# sb4.net
KiCad netlist of a schematic drawn in EAGLE
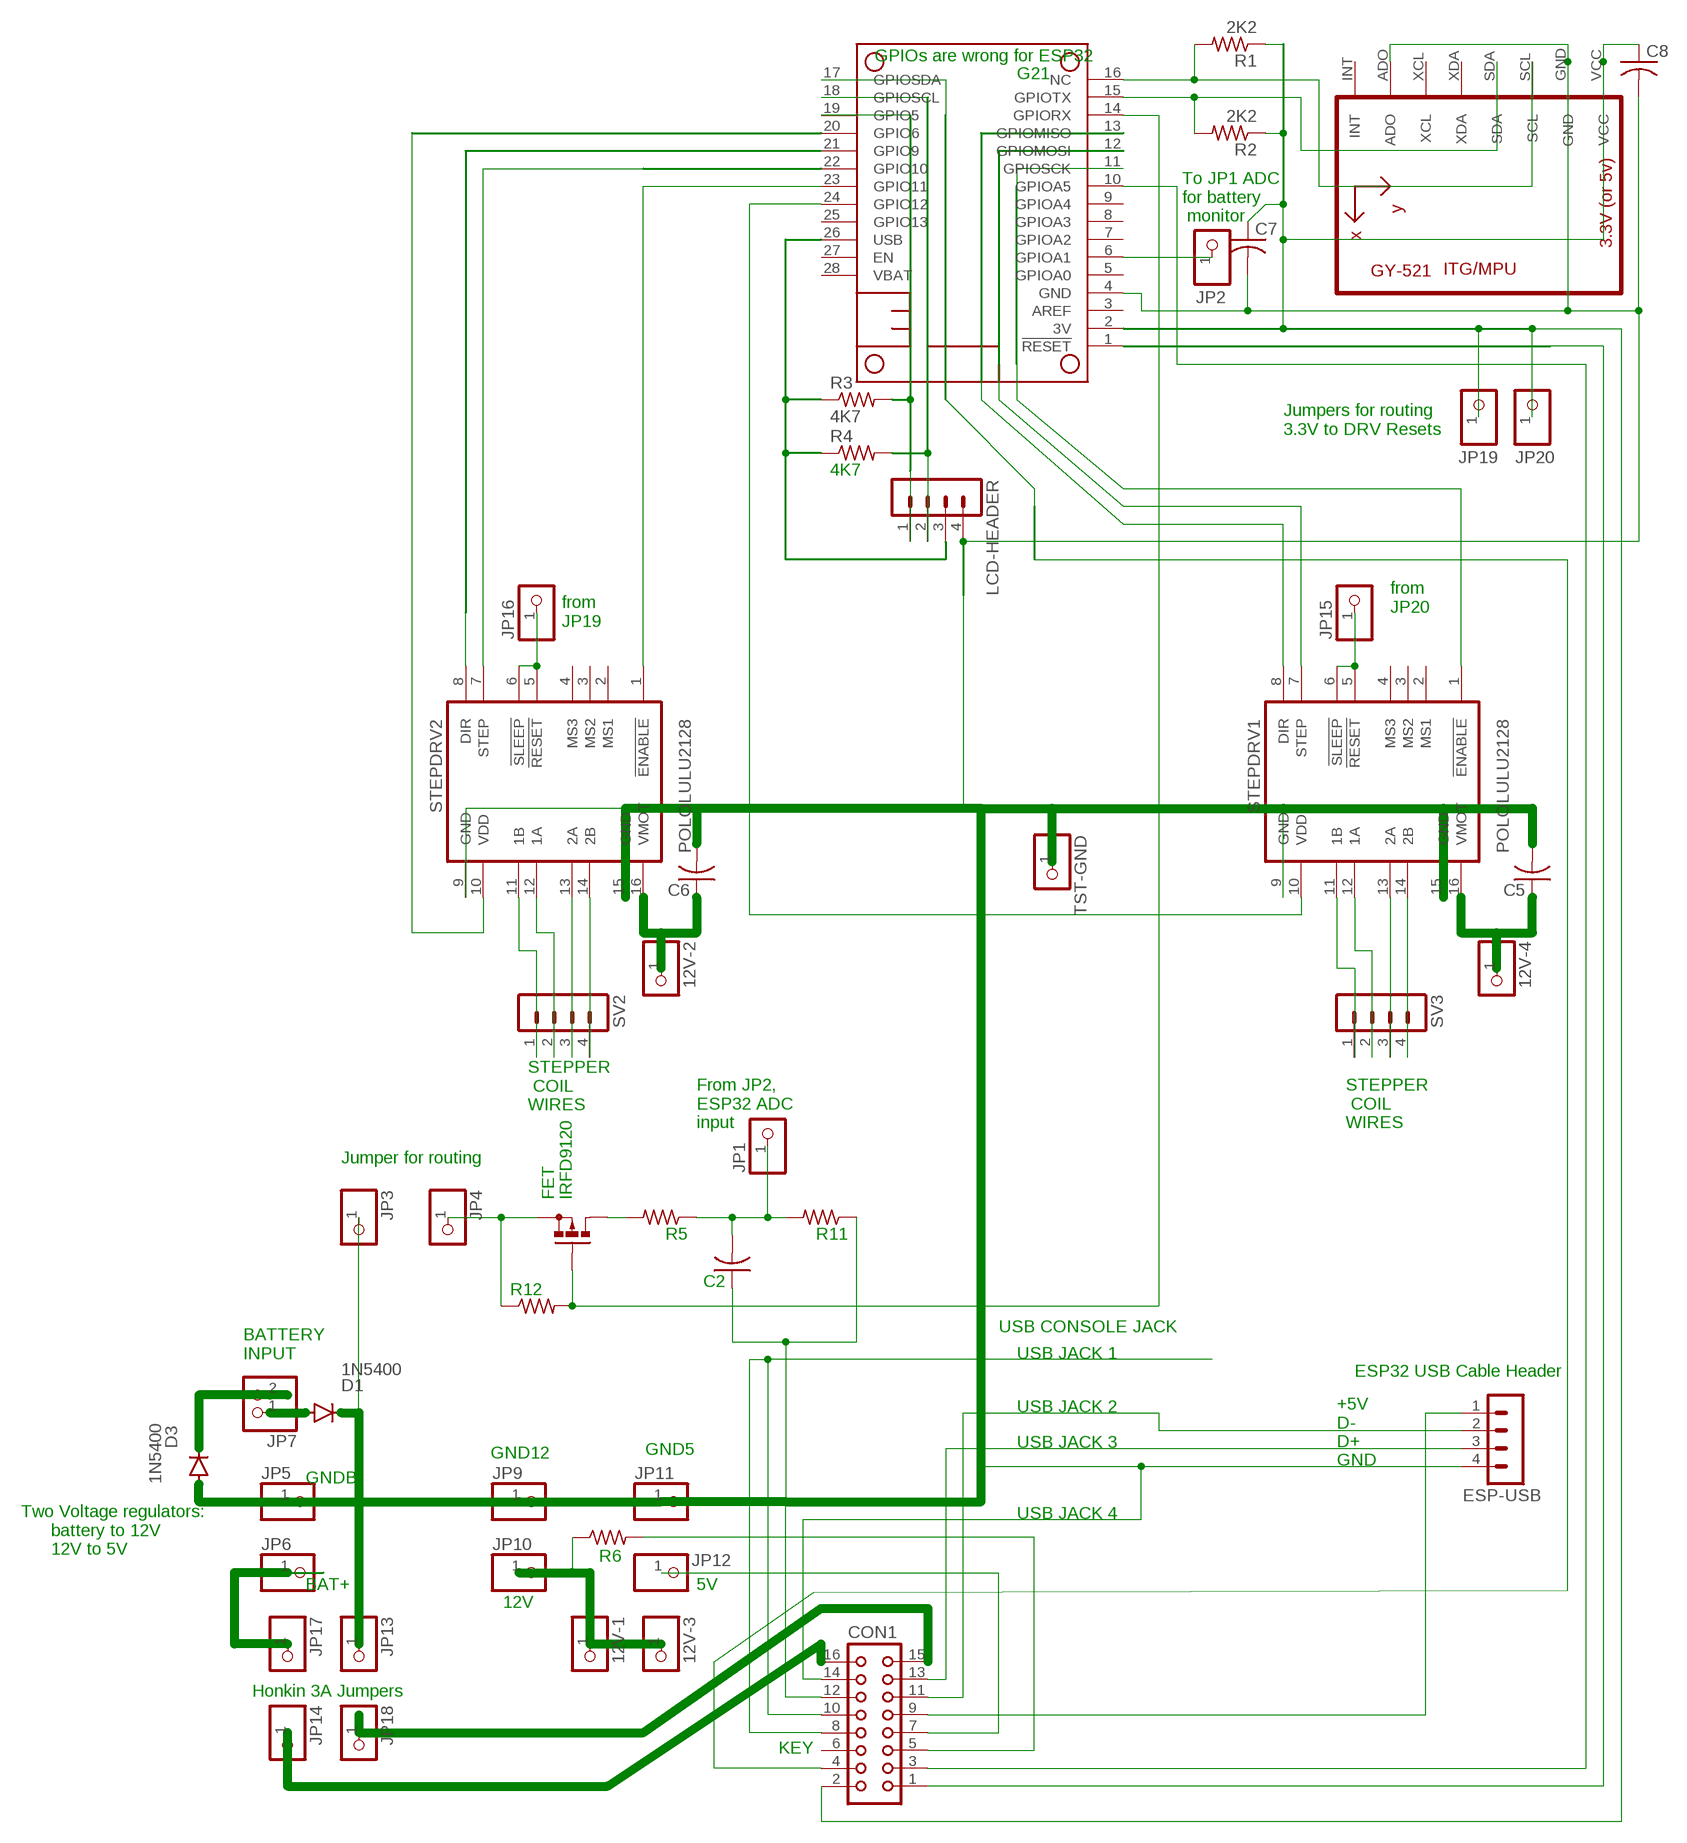
[diagram p0: schematic, sheet 1]

(export (version "E")
  (design (tool "Eeschema 10.0.6"))
  (components
    (comp (ref "12V-1")
      (value "PINHD-1X1")
      (footprint "eagle-import:1X01")
      (libsource (lib "eagle-import") (part "PINHD-1X1"))
    )
    (comp (ref "12V-2")
      (value "PINHD-1X1")
      (footprint "eagle-import:1X01")
      (libsource (lib "eagle-import") (part "PINHD-1X1"))
    )
    (comp (ref "12V-3")
      (value "PINHD-1X1")
      (footprint "eagle-import:1X01")
      (libsource (lib "eagle-import") (part "PINHD-1X1"))
    )
    (comp (ref "12V-4")
      (value "PINHD-1X1")
      (footprint "eagle-import:1X01")
      (libsource (lib "eagle-import") (part "PINHD-1X1"))
    )
    (comp (ref "C2")
      (value "C-US050-025X075")
      (footprint "eagle-import:C050-025X075")
      (libsource (lib "eagle-import") (part "C-US050-025X075"))
    )
    (comp (ref "C5")
      (value "C-US050-024X044")
      (footprint "eagle-import:C050-024X044")
      (libsource (lib "eagle-import") (part "C-US050-024X044"))
    )
    (comp (ref "C6")
      (value "C-US050-024X044")
      (footprint "eagle-import:C050-024X044")
      (libsource (lib "eagle-import") (part "C-US050-024X044"))
    )
    (comp (ref "C7")
      (value "C-US050-024X044")
      (footprint "eagle-import:C050-024X044")
      (libsource (lib "eagle-import") (part "C-US050-024X044"))
    )
    (comp (ref "C8")
      (value "C-US050-024X044")
      (footprint "eagle-import:C050-024X044")
      (libsource (lib "eagle-import") (part "C-US050-024X044"))
    )
    (comp (ref "CON1")
      (value "CON16")
      (footprint "eagle-import:CON16")
      (libsource (lib "eagle-import") (part "CON16"))
    )
    (comp (ref "D1")
      (value "1N5400")
      (footprint "eagle-import:DO201-15")
      (libsource (lib "eagle-import") (part "1N5400"))
    )
    (comp (ref "D3")
      (value "1N5400")
      (footprint "eagle-import:DO201-15")
      (libsource (lib "eagle-import") (part "1N5400"))
    )
    (comp (ref "ESP-USB")
      (value "MA04-1")
      (footprint "eagle-import:MA04-1")
      (libsource (lib "eagle-import") (part "MA04-1"))
    )
    (comp (ref "FET")
      (value "IRFD9120")
      (footprint "eagle-import:C370-01")
      (libsource (lib "eagle-import") (part "IRFD9120"))
    )
    (comp (ref "JP1")
      (value "PINHD-1X1")
      (footprint "eagle-import:1X01")
      (libsource (lib "eagle-import") (part "PINHD-1X1"))
    )
    (comp (ref "JP2")
      (value "PINHD-1X1")
      (footprint "eagle-import:1X01")
      (libsource (lib "eagle-import") (part "PINHD-1X1"))
    )
    (comp (ref "JP3")
      (value "PINHD-1X1")
      (footprint "eagle-import:1X01")
      (libsource (lib "eagle-import") (part "PINHD-1X1"))
    )
    (comp (ref "JP4")
      (value "PINHD-1X1")
      (footprint "eagle-import:1X01")
      (libsource (lib "eagle-import") (part "PINHD-1X1"))
    )
    (comp (ref "JP5")
      (value "PINHD-1X1")
      (footprint "eagle-import:1X01")
      (libsource (lib "eagle-import") (part "PINHD-1X1"))
    )
    (comp (ref "JP6")
      (value "PINHD-1X1")
      (footprint "eagle-import:1X01")
      (libsource (lib "eagle-import") (part "PINHD-1X1"))
    )
    (comp (ref "JP7")
      (value "PINHD-1X2")
      (footprint "eagle-import:1X02")
      (libsource (lib "eagle-import") (part "PINHD-1X2"))
    )
    (comp (ref "JP9")
      (value "PINHD-1X1")
      (footprint "eagle-import:1X01")
      (libsource (lib "eagle-import") (part "PINHD-1X1"))
    )
    (comp (ref "JP10")
      (value "PINHD-1X1")
      (footprint "eagle-import:1X01")
      (libsource (lib "eagle-import") (part "PINHD-1X1"))
    )
    (comp (ref "JP11")
      (value "PINHD-1X1")
      (footprint "eagle-import:1X01")
      (libsource (lib "eagle-import") (part "PINHD-1X1"))
    )
    (comp (ref "JP12")
      (value "PINHD-1X1")
      (footprint "eagle-import:1X01")
      (libsource (lib "eagle-import") (part "PINHD-1X1"))
    )
    (comp (ref "JP13")
      (value "PINHD-1X1")
      (footprint "eagle-import:1X01")
      (libsource (lib "eagle-import") (part "PINHD-1X1"))
    )
    (comp (ref "JP14")
      (value "PINHD-1X1")
      (footprint "eagle-import:1X01")
      (libsource (lib "eagle-import") (part "PINHD-1X1"))
    )
    (comp (ref "JP15")
      (value "PINHD-1X1")
      (footprint "eagle-import:1X01")
      (libsource (lib "eagle-import") (part "PINHD-1X1"))
    )
    (comp (ref "JP16")
      (value "PINHD-1X1")
      (footprint "eagle-import:1X01")
      (libsource (lib "eagle-import") (part "PINHD-1X1"))
    )
    (comp (ref "JP17")
      (value "PINHD-1X1")
      (footprint "eagle-import:1X01")
      (libsource (lib "eagle-import") (part "PINHD-1X1"))
    )
    (comp (ref "JP18")
      (value "PINHD-1X1")
      (footprint "eagle-import:1X01")
      (libsource (lib "eagle-import") (part "PINHD-1X1"))
    )
    (comp (ref "JP19")
      (value "PINHD-1X1")
      (footprint "eagle-import:1X01")
      (libsource (lib "eagle-import") (part "PINHD-1X1"))
    )
    (comp (ref "JP20")
      (value "PINHD-1X1")
      (footprint "eagle-import:1X01")
      (libsource (lib "eagle-import") (part "PINHD-1X1"))
    )
    (comp (ref "LCD-HEADER")
      (value "MA04-1")
      (footprint "eagle-import:MA04-1")
      (libsource (lib "eagle-import") (part "MA04-1"))
    )
    (comp (ref "MS2")
      (value "FEATHERWING_NOHOLES")
      (footprint "eagle-import:FEATHERWING_NOHOLES")
      (libsource (lib "eagle-import") (part "FEATHERWING_NOHOLES"))
    )
    (comp (ref "R1")
      (value "2K2")
      (footprint "eagle-import:0309_12")
      (libsource (lib "eagle-import") (part "resistor_348_R-US_0309/12"))
    )
    (comp (ref "R2")
      (value "2K2")
      (footprint "eagle-import:0309_12")
      (libsource (lib "eagle-import") (part "resistor_348_R-US_0309/12"))
    )
    (comp (ref "R3")
      (value "4K7")
      (footprint "eagle-import:0309_12")
      (libsource (lib "eagle-import") (part "resistor_348_R-US_0309/12"))
    )
    (comp (ref "R4")
      (value "4K7")
      (footprint "eagle-import:0309_12")
      (libsource (lib "eagle-import") (part "resistor_348_R-US_0309/12"))
    )
    (comp (ref "R5")
      (value "R-US_0207/10")
      (footprint "eagle-import:0207_10")
      (libsource (lib "eagle-import") (part "R-US_0207/10"))
    )
    (comp (ref "R6")
      (value "R-US_0207/10")
      (footprint "eagle-import:0207_10")
      (libsource (lib "eagle-import") (part "R-US_0207/10"))
    )
    (comp (ref "R11")
      (value "R-US_0207/10")
      (footprint "eagle-import:0207_10")
      (libsource (lib "eagle-import") (part "R-US_0207/10"))
    )
    (comp (ref "R12")
      (value "R-US_0207/10")
      (footprint "eagle-import:0207_10")
      (libsource (lib "eagle-import") (part "R-US_0207/10"))
    )
    (comp (ref "STEPDRV1")
      (value "POLOLULU2128")
      (footprint "eagle-import:POLOLULU2128")
      (libsource (lib "eagle-import") (part "POLOLULU2128"))
    )
    (comp (ref "STEPDRV2")
      (value "POLOLULU2128")
      (footprint "eagle-import:POLOLULU2128")
      (libsource (lib "eagle-import") (part "POLOLULU2128"))
    )
    (comp (ref "SV2")
      (value "MA04-1")
      (footprint "eagle-import:MA04-1")
      (libsource (lib "eagle-import") (part "MA04-1"))
    )
    (comp (ref "SV3")
      (value "MA04-1")
      (footprint "eagle-import:MA04-1")
      (libsource (lib "eagle-import") (part "MA04-1"))
    )
    (comp (ref "TST-GND")
      (value "PINHD-1X1")
      (footprint "eagle-import:1X01")
      (libsource (lib "eagle-import") (part "PINHD-1X1"))
    )
    (comp (ref "U1")
      (value "GY-521MPU6050")
      (footprint "eagle-import:GY-521")
      (libsource (lib "eagle-import") (part "GY-521MPU6050"))
    )
  )
  (nets
    (net (code "1") (name "/VBAT") (class "Default")
      (node (ref "MS2") (pin "28") (pinfunction "VBAT_28") (pintype "power_in"))
    )
    (net (code "2") (name "Net-(12V-1-Pad1)") (class "Default")
      (node (ref "12V-1") (pin "1") (pinfunction "1_1") (pintype "passive"))
      (node (ref "12V-3") (pin "1") (pinfunction "1_1") (pintype "passive"))
      (node (ref "JP10") (pin "1") (pinfunction "1_1") (pintype "passive"))
      (node (ref "R6") (pin "1") (pinfunction "1_1") (pintype "passive"))
    )
    (net (code "3") (name "Net-(C2-Pad2)") (class "Default")
      (node (ref "C2") (pin "2") (pinfunction "2_2") (pintype "passive"))
      (node (ref "JP1") (pin "1") (pinfunction "1_1") (pintype "passive"))
      (node (ref "R11") (pin "2") (pinfunction "2_2") (pintype "passive"))
      (node (ref "R5") (pin "1") (pinfunction "1_1") (pintype "passive"))
    )
    (net (code "4") (name "Net-(CON1-Pad5)") (class "Default")
      (node (ref "CON1") (pin "5") (pinfunction "5_5") (pintype "passive"))
      (node (ref "R6") (pin "2") (pinfunction "2_2") (pintype "passive"))
    )
    (net (code "5") (name "Net-(CON1-Pad7)") (class "Default")
      (node (ref "CON1") (pin "7") (pinfunction "7_7") (pintype "passive"))
      (node (ref "JP12") (pin "1") (pinfunction "1_1") (pintype "passive"))
    )
    (net (code "6") (name "Net-(CON1-Pad9)") (class "Default")
      (node (ref "CON1") (pin "9") (pinfunction "9_9") (pintype "passive"))
      (node (ref "ESP-USB") (pin "1") (pinfunction "1_1") (pintype "passive"))
    )
    (net (code "7") (name "Net-(CON1-Pad10)") (class "Default")
      (node (ref "CON1") (pin "10") (pinfunction "10_10") (pintype "passive"))
      (node (ref "CON1") (pin "8") (pinfunction "8_8") (pintype "passive"))
    )
    (net (code "8") (name "Net-(CON1-Pad11)") (class "Default")
      (node (ref "CON1") (pin "11") (pinfunction "11_11") (pintype "passive"))
      (node (ref "ESP-USB") (pin "2") (pinfunction "2_2") (pintype "passive"))
    )
    (net (code "9") (name "Net-(CON1-Pad13)") (class "Default")
      (node (ref "CON1") (pin "13") (pinfunction "13_13") (pintype "passive"))
      (node (ref "ESP-USB") (pin "3") (pinfunction "3_3") (pintype "passive"))
    )
    (net (code "10") (name "Net-(CON1-Pad15)") (class "Default")
      (node (ref "CON1") (pin "15") (pinfunction "15_15") (pintype "passive"))
      (node (ref "JP18") (pin "1") (pinfunction "1_1") (pintype "passive"))
    )
    (net (code "11") (name "Net-(CON1-Pad16)") (class "Default")
      (node (ref "CON1") (pin "16") (pinfunction "16_16") (pintype "passive"))
      (node (ref "JP14") (pin "1") (pinfunction "1_1") (pintype "passive"))
    )
    (net (code "12") (name "Net-(D1-PadA)") (class "Default")
      (node (ref "D1") (pin "A") (pinfunction "A_A") (pintype "passive"))
      (node (ref "JP7") (pin "1") (pinfunction "1_1") (pintype "passive"))
    )
    (net (code "13") (name "Net-(D1-PadC)") (class "Default")
      (node (ref "D1") (pin "C") (pinfunction "C_C") (pintype "passive"))
      (node (ref "JP13") (pin "1") (pinfunction "1_1") (pintype "passive"))
      (node (ref "JP3") (pin "1") (pinfunction "1_1") (pintype "passive"))
    )
    (net (code "14") (name "Net-(D3-PadC)") (class "Default")
      (node (ref "D3") (pin "C") (pinfunction "C_C") (pintype "passive"))
      (node (ref "JP7") (pin "2") (pinfunction "2_2") (pintype "passive"))
    )
    (net (code "15") (name "Net-(FET-D-PadD1)") (class "Default")
      (node (ref "FET") (pin "D") (pinfunction "D_D") (pintype "passive"))
      (node (ref "FET") (pin "D1") (pinfunction "D_D1") (pintype "passive"))
      (node (ref "R5") (pin "2") (pinfunction "2_2") (pintype "passive"))
    )
    (net (code "16") (name "Net-(FET-PadS)") (class "Default")
      (node (ref "FET") (pin "S") (pinfunction "S_S") (pintype "passive"))
      (node (ref "JP4") (pin "1") (pinfunction "1_1") (pintype "passive"))
      (node (ref "R12") (pin "1") (pinfunction "1_1") (pintype "passive"))
    )
    (net (code "17") (name "Net-(JP17-Pad1)") (class "Default")
      (node (ref "JP17") (pin "1") (pinfunction "1_1") (pintype "passive"))
      (node (ref "JP6") (pin "1") (pinfunction "1_1") (pintype "passive"))
    )
    (net (code "18") (name "Net-(MS2-3V)") (class "Default")
      (node (ref "C7") (pin "1") (pinfunction "1_1") (pintype "passive"))
      (node (ref "C8") (pin "1") (pinfunction "1_1") (pintype "passive"))
      (node (ref "CON1") (pin "2") (pinfunction "2_2") (pintype "passive"))
      (node (ref "JP19") (pin "1") (pinfunction "1_1") (pintype "passive"))
      (node (ref "JP20") (pin "1") (pinfunction "1_1") (pintype "passive"))
      (node (ref "MS2") (pin "2") (pinfunction "3V_2") (pintype "power_in"))
      (node (ref "R1") (pin "1") (pinfunction "1_1") (pintype "passive"))
      (node (ref "R2") (pin "1") (pinfunction "1_1") (pintype "passive"))
      (node (ref "U1") (pin "VCC") (pinfunction "VCC_VCC") (pintype "bidirectional"))
    )
    (net (code "19") (name "Net-(MS2-GND)") (class "Default")
      (node (ref "C2") (pin "1") (pinfunction "1_1") (pintype "passive"))
      (node (ref "C5") (pin "2") (pinfunction "2_2") (pintype "passive"))
      (node (ref "C6") (pin "2") (pinfunction "2_2") (pintype "passive"))
      (node (ref "C7") (pin "2") (pinfunction "2_2") (pintype "passive"))
      (node (ref "C8") (pin "2") (pinfunction "2_2") (pintype "passive"))
      (node (ref "CON1") (pin "12") (pinfunction "12_12") (pintype "passive"))
      (node (ref "CON1") (pin "14") (pinfunction "14_14") (pintype "passive"))
      (node (ref "D3") (pin "A") (pinfunction "A_A") (pintype "passive"))
      (node (ref "ESP-USB") (pin "4") (pinfunction "4_4") (pintype "passive"))
      (node (ref "JP11") (pin "1") (pinfunction "1_1") (pintype "passive"))
      (node (ref "JP5") (pin "1") (pinfunction "1_1") (pintype "passive"))
      (node (ref "JP9") (pin "1") (pinfunction "1_1") (pintype "passive"))
      (node (ref "LCD-HEADER") (pin "4") (pinfunction "4_4") (pintype "passive"))
      (node (ref "MS2") (pin "4") (pinfunction "GND_4") (pintype "power_in"))
      (node (ref "R11") (pin "1") (pinfunction "1_1") (pintype "passive"))
      (node (ref "STEPDRV1") (pin "15") (pinfunction "GND_15") (pintype "power_in"))
      (node (ref "STEPDRV1") (pin "9") (pinfunction "GND_9") (pintype "power_in"))
      (node (ref "STEPDRV2") (pin "15") (pinfunction "GND_15") (pintype "power_in"))
      (node (ref "STEPDRV2") (pin "9") (pinfunction "GND_9") (pintype "power_in"))
      (node (ref "TST-GND") (pin "1") (pinfunction "1_1") (pintype "passive"))
      (node (ref "U1") (pin "ADO") (pinfunction "ADO_ADO") (pintype "bidirectional"))
      (node (ref "U1") (pin "GND") (pinfunction "GND_GND") (pintype "bidirectional"))
    )
    (net (code "20") (name "Net-(MS2-GPIO5)") (class "Default")
      (node (ref "LCD-HEADER") (pin "1") (pinfunction "1_1") (pintype "passive"))
      (node (ref "MS2") (pin "19") (pinfunction "GPIO5_19") (pintype "bidirectional"))
      (node (ref "R3") (pin "2") (pinfunction "2_2") (pintype "passive"))
    )
    (net (code "21") (name "Net-(MS2-GPIO6)") (class "Default")
      (node (ref "MS2") (pin "20") (pinfunction "GPIO6_20") (pintype "bidirectional"))
      (node (ref "STEPDRV2") (pin "10") (pinfunction "VDD_10") (pintype "power_in"))
    )
    (net (code "22") (name "Net-(MS2-GPIO9)") (class "Default")
      (node (ref "MS2") (pin "21") (pinfunction "GPIO9_21") (pintype "bidirectional"))
      (node (ref "STEPDRV2") (pin "8") (pinfunction "DIR_8") (pintype "input"))
    )
    (net (code "23") (name "Net-(MS2-GPIO10)") (class "Default")
      (node (ref "MS2") (pin "22") (pinfunction "GPIO10_22") (pintype "bidirectional"))
      (node (ref "STEPDRV2") (pin "7") (pinfunction "STEP_7") (pintype "input"))
    )
    (net (code "24") (name "Net-(MS2-GPIO11)") (class "Default")
      (node (ref "MS2") (pin "23") (pinfunction "GPIO11_23") (pintype "bidirectional"))
      (node (ref "STEPDRV2") (pin "1") (pinfunction "~{ENABLE}_1") (pintype "input"))
    )
    (net (code "25") (name "Net-(MS2-GPIO12)") (class "Default")
      (node (ref "MS2") (pin "24") (pinfunction "GPIO12_24") (pintype "bidirectional"))
      (node (ref "STEPDRV1") (pin "10") (pinfunction "VDD_10") (pintype "power_in"))
    )
    (net (code "26") (name "Net-(MS2-GPIOA1)") (class "Default")
      (node (ref "JP2") (pin "1") (pinfunction "1_1") (pintype "passive"))
      (node (ref "MS2") (pin "6") (pinfunction "GPIOA1_6") (pintype "bidirectional"))
    )
    (net (code "27") (name "Net-(MS2-GPIOA5)") (class "Default")
      (node (ref "CON1") (pin "3") (pinfunction "3_3") (pintype "passive"))
      (node (ref "MS2") (pin "10") (pinfunction "GPIOA5_10") (pintype "bidirectional"))
    )
    (net (code "28") (name "Net-(MS2-GPIOMISO)") (class "Default")
      (node (ref "MS2") (pin "13") (pinfunction "GPIOMISO_13") (pintype "bidirectional"))
      (node (ref "STEPDRV1") (pin "8") (pinfunction "DIR_8") (pintype "input"))
    )
    (net (code "29") (name "Net-(MS2-GPIOMOSI)") (class "Default")
      (node (ref "MS2") (pin "12") (pinfunction "GPIOMOSI_12") (pintype "bidirectional"))
      (node (ref "STEPDRV1") (pin "7") (pinfunction "STEP_7") (pintype "input"))
    )
    (net (code "30") (name "Net-(MS2-GPIORX)") (class "Default")
      (node (ref "FET") (pin "G") (pinfunction "G_G") (pintype "passive"))
      (node (ref "MS2") (pin "14") (pinfunction "GPIORX_14") (pintype "bidirectional"))
      (node (ref "R12") (pin "2") (pinfunction "2_2") (pintype "passive"))
    )
    (net (code "31") (name "Net-(MS2-GPIOSCK)") (class "Default")
      (node (ref "MS2") (pin "11") (pinfunction "GPIOSCK_11") (pintype "bidirectional"))
      (node (ref "STEPDRV1") (pin "1") (pinfunction "~{ENABLE}_1") (pintype "input"))
    )
    (net (code "32") (name "Net-(MS2-GPIOSCL)") (class "Default")
      (node (ref "LCD-HEADER") (pin "2") (pinfunction "2_2") (pintype "passive"))
      (node (ref "MS2") (pin "18") (pinfunction "GPIOSCL_18") (pintype "bidirectional"))
      (node (ref "R4") (pin "2") (pinfunction "2_2") (pintype "passive"))
    )
    (net (code "33") (name "Net-(MS2-GPIOSDA)") (class "Default")
      (node (ref "CON1") (pin "4") (pinfunction "4_4") (pintype "passive"))
      (node (ref "MS2") (pin "17") (pinfunction "GPIOSDA_17") (pintype "bidirectional"))
    )
    (net (code "34") (name "Net-(MS2-GPIOTX)") (class "Default")
      (node (ref "MS2") (pin "15") (pinfunction "GPIOTX_15") (pintype "bidirectional"))
      (node (ref "R2") (pin "2") (pinfunction "2_2") (pintype "passive"))
      (node (ref "U1") (pin "SDA") (pinfunction "SDA_SDA") (pintype "bidirectional"))
    )
    (net (code "35") (name "Net-(MS2-NC)") (class "Default")
      (node (ref "MS2") (pin "16") (pinfunction "NC_16") (pintype "passive"))
      (node (ref "R1") (pin "2") (pinfunction "2_2") (pintype "passive"))
      (node (ref "U1") (pin "SCL") (pinfunction "SCL_SCL") (pintype "bidirectional"))
    )
    (net (code "36") (name "Net-(MS2-USB)") (class "Default")
      (node (ref "LCD-HEADER") (pin "3") (pinfunction "3_3") (pintype "passive"))
      (node (ref "MS2") (pin "26") (pinfunction "USB_26") (pintype "power_in"))
      (node (ref "R3") (pin "1") (pinfunction "1_1") (pintype "passive"))
      (node (ref "R4") (pin "1") (pinfunction "1_1") (pintype "passive"))
    )
    (net (code "37") (name "Net-(MS2-~{RESET})") (class "Default")
      (node (ref "CON1") (pin "1") (pinfunction "1_1") (pintype "passive"))
      (node (ref "MS2") (pin "1") (pinfunction "~{RESET}_1") (pintype "input"))
    )
    (net (code "38") (name "Net-(STEPDRV1-1A)") (class "Default")
      (node (ref "STEPDRV1") (pin "12") (pinfunction "1A_12") (pintype "output"))
      (node (ref "SV3") (pin "2") (pinfunction "2_2") (pintype "passive"))
    )
    (net (code "39") (name "Net-(STEPDRV1-1B)") (class "Default")
      (node (ref "STEPDRV1") (pin "11") (pinfunction "1B_11") (pintype "output"))
      (node (ref "SV3") (pin "1") (pinfunction "1_1") (pintype "passive"))
    )
    (net (code "40") (name "Net-(STEPDRV1-2A)") (class "Default")
      (node (ref "STEPDRV1") (pin "13") (pinfunction "2A_13") (pintype "output"))
      (node (ref "SV3") (pin "3") (pinfunction "3_3") (pintype "passive"))
    )
    (net (code "41") (name "Net-(STEPDRV1-2B)") (class "Default")
      (node (ref "STEPDRV1") (pin "14") (pinfunction "2B_14") (pintype "output"))
      (node (ref "SV3") (pin "4") (pinfunction "4_4") (pintype "passive"))
    )
    (net (code "42") (name "Net-(STEPDRV1-VMOT)") (class "Default")
      (node (ref "12V-4") (pin "1") (pinfunction "1_1") (pintype "passive"))
      (node (ref "C5") (pin "1") (pinfunction "1_1") (pintype "passive"))
      (node (ref "STEPDRV1") (pin "16") (pinfunction "VMOT_16") (pintype "power_in"))
    )
    (net (code "43") (name "Net-(STEPDRV1-~{RESET})") (class "Default")
      (node (ref "JP15") (pin "1") (pinfunction "1_1") (pintype "passive"))
      (node (ref "STEPDRV1") (pin "5") (pinfunction "~{RESET}_5") (pintype "input"))
      (node (ref "STEPDRV1") (pin "6") (pinfunction "~{SLEEP}_6") (pintype "input"))
    )
    (net (code "44") (name "Net-(STEPDRV2-1A)") (class "Default")
      (node (ref "STEPDRV2") (pin "12") (pinfunction "1A_12") (pintype "output"))
      (node (ref "SV2") (pin "2") (pinfunction "2_2") (pintype "passive"))
    )
    (net (code "45") (name "Net-(STEPDRV2-1B)") (class "Default")
      (node (ref "STEPDRV2") (pin "11") (pinfunction "1B_11") (pintype "output"))
      (node (ref "SV2") (pin "1") (pinfunction "1_1") (pintype "passive"))
    )
    (net (code "46") (name "Net-(STEPDRV2-2A)") (class "Default")
      (node (ref "STEPDRV2") (pin "13") (pinfunction "2A_13") (pintype "output"))
      (node (ref "SV2") (pin "3") (pinfunction "3_3") (pintype "passive"))
    )
    (net (code "47") (name "Net-(STEPDRV2-2B)") (class "Default")
      (node (ref "STEPDRV2") (pin "14") (pinfunction "2B_14") (pintype "output"))
      (node (ref "SV2") (pin "4") (pinfunction "4_4") (pintype "passive"))
    )
    (net (code "48") (name "Net-(STEPDRV2-VMOT)") (class "Default")
      (node (ref "12V-2") (pin "1") (pinfunction "1_1") (pintype "passive"))
      (node (ref "C6") (pin "1") (pinfunction "1_1") (pintype "passive"))
      (node (ref "STEPDRV2") (pin "16") (pinfunction "VMOT_16") (pintype "power_in"))
    )
    (net (code "49") (name "Net-(STEPDRV2-~{RESET})") (class "Default")
      (node (ref "JP16") (pin "1") (pinfunction "1_1") (pintype "passive"))
      (node (ref "STEPDRV2") (pin "5") (pinfunction "~{RESET}_5") (pintype "input"))
      (node (ref "STEPDRV2") (pin "6") (pinfunction "~{SLEEP}_6") (pintype "input"))
    )
    (net (code "50") (name "unconnected-(CON1-Pad6)") (class "Default")
      (node (ref "CON1") (pin "6") (pinfunction "6_6") (pintype "passive"))
    )
    (net (code "51") (name "unconnected-(MS2-AREF-Pad3)") (class "Default")
      (node (ref "MS2") (pin "3") (pinfunction "AREF_3") (pintype "passive"))
    )
    (net (code "52") (name "unconnected-(MS2-EN-Pad27)") (class "Default")
      (node (ref "MS2") (pin "27") (pinfunction "EN_27") (pintype "passive"))
    )
    (net (code "53") (name "unconnected-(MS2-GPIO13-Pad25)") (class "Default")
      (node (ref "MS2") (pin "25") (pinfunction "GPIO13_25") (pintype "bidirectional"))
    )
    (net (code "54") (name "unconnected-(MS2-GPIOA0-Pad5)") (class "Default")
      (node (ref "MS2") (pin "5") (pinfunction "GPIOA0_5") (pintype "bidirectional"))
    )
    (net (code "55") (name "unconnected-(MS2-GPIOA2-Pad7)") (class "Default")
      (node (ref "MS2") (pin "7") (pinfunction "GPIOA2_7") (pintype "bidirectional"))
    )
    (net (code "56") (name "unconnected-(MS2-GPIOA3-Pad8)") (class "Default")
      (node (ref "MS2") (pin "8") (pinfunction "GPIOA3_8") (pintype "bidirectional"))
    )
    (net (code "57") (name "unconnected-(MS2-GPIOA4-Pad9)") (class "Default")
      (node (ref "MS2") (pin "9") (pinfunction "GPIOA4_9") (pintype "bidirectional"))
    )
    (net (code "58") (name "unconnected-(STEPDRV1-MS1-Pad2)") (class "Default")
      (node (ref "STEPDRV1") (pin "2") (pinfunction "MS1_2") (pintype "input"))
    )
    (net (code "59") (name "unconnected-(STEPDRV1-MS2-Pad3)") (class "Default")
      (node (ref "STEPDRV1") (pin "3") (pinfunction "MS2_3") (pintype "input"))
    )
    (net (code "60") (name "unconnected-(STEPDRV1-MS3-Pad4)") (class "Default")
      (node (ref "STEPDRV1") (pin "4") (pinfunction "MS3_4") (pintype "input"))
    )
    (net (code "61") (name "unconnected-(STEPDRV2-MS1-Pad2)") (class "Default")
      (node (ref "STEPDRV2") (pin "2") (pinfunction "MS1_2") (pintype "input"))
    )
    (net (code "62") (name "unconnected-(STEPDRV2-MS2-Pad3)") (class "Default")
      (node (ref "STEPDRV2") (pin "3") (pinfunction "MS2_3") (pintype "input"))
    )
    (net (code "63") (name "unconnected-(STEPDRV2-MS3-Pad4)") (class "Default")
      (node (ref "STEPDRV2") (pin "4") (pinfunction "MS3_4") (pintype "input"))
    )
    (net (code "64") (name "unconnected-(U1-PadINT)") (class "Default")
      (node (ref "U1") (pin "INT") (pinfunction "INT_INT") (pintype "bidirectional"))
    )
    (net (code "65") (name "unconnected-(U1-PadXCL)") (class "Default")
      (node (ref "U1") (pin "XCL") (pinfunction "XCL_XCL") (pintype "bidirectional"))
    )
    (net (code "66") (name "unconnected-(U1-PadXDA)") (class "Default")
      (node (ref "U1") (pin "XDA") (pinfunction "XDA_XDA") (pintype "bidirectional"))
    )
  )
)
